# BOARD4.net
KiCad netlist of a schematic drawn in EAGLE
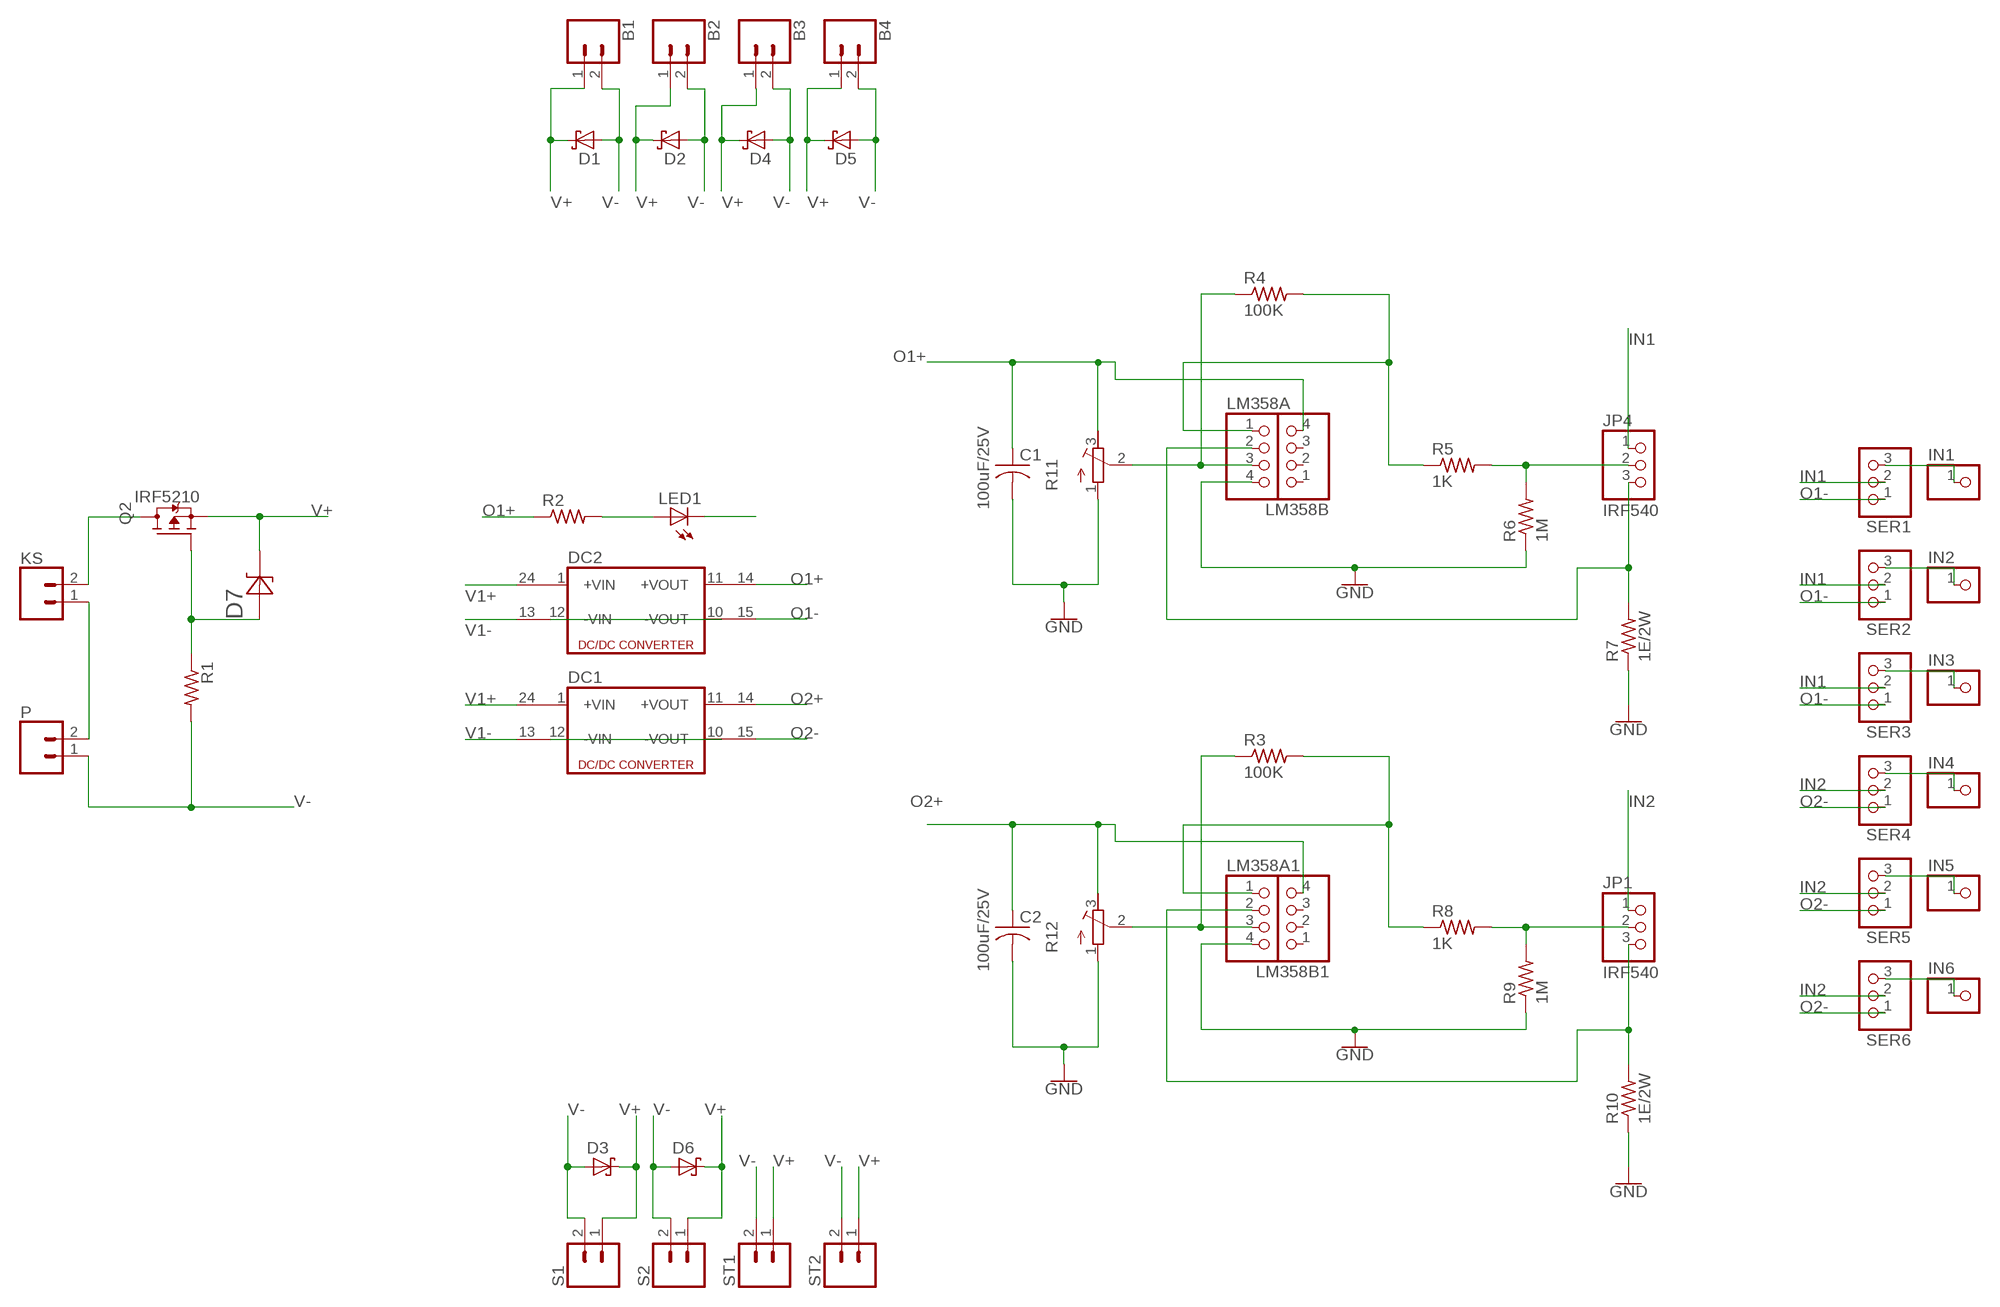
[diagram p0: schematic, sheet 1]

(export (version "E")
  (design (tool "Eeschema 10.0.6"))
  (components
    (comp (ref "B1")
      (value "CONN_02")
      (footprint "eagle-import:1X02")
      (libsource (lib "eagle-import") (part "CONN_02"))
    )
    (comp (ref "B2")
      (value "CONN_02")
      (footprint "eagle-import:1X02")
      (libsource (lib "eagle-import") (part "CONN_02"))
    )
    (comp (ref "B3")
      (value "CONN_02")
      (footprint "eagle-import:1X02")
      (libsource (lib "eagle-import") (part "CONN_02"))
    )
    (comp (ref "B4")
      (value "CONN_02")
      (footprint "eagle-import:1X02")
      (libsource (lib "eagle-import") (part "CONN_02"))
    )
    (comp (ref "C1")
      (value "100uF/25V")
      (footprint "eagle-import:C025-024X044")
      (libsource (lib "eagle-import") (part "C-US025-024X044"))
    )
    (comp (ref "C2")
      (value "100uF/25V")
      (footprint "eagle-import:C025-024X044")
      (libsource (lib "eagle-import") (part "C-US025-024X044"))
    )
    (comp (ref "D1")
      (value "SCHOTTKY-DIODEF126Z12")
      (footprint "eagle-import:F126Z12")
      (libsource (lib "eagle-import") (part "SCHOTTKY-DIODEF126Z12"))
    )
    (comp (ref "D2")
      (value "SCHOTTKY-DIODEF126Z12")
      (footprint "eagle-import:F126Z12")
      (libsource (lib "eagle-import") (part "SCHOTTKY-DIODEF126Z12"))
    )
    (comp (ref "D3")
      (value "SCHOTTKY-DIODEF126Z12")
      (footprint "eagle-import:F126Z12")
      (libsource (lib "eagle-import") (part "SCHOTTKY-DIODEF126Z12"))
    )
    (comp (ref "D4")
      (value "SCHOTTKY-DIODEF126Z12")
      (footprint "eagle-import:F126Z12")
      (libsource (lib "eagle-import") (part "SCHOTTKY-DIODEF126Z12"))
    )
    (comp (ref "D5")
      (value "SCHOTTKY-DIODEF126Z12")
      (footprint "eagle-import:F126Z12")
      (libsource (lib "eagle-import") (part "SCHOTTKY-DIODEF126Z12"))
    )
    (comp (ref "D6")
      (value "SCHOTTKY-DIODEF126Z12")
      (footprint "eagle-import:F126Z12")
      (libsource (lib "eagle-import") (part "SCHOTTKY-DIODEF126Z12"))
    )
    (comp (ref "D7")
      (value "1N4752A-T")
      (footprint "eagle-import:DIOAD1060W80L410D260")
      (fields (field (name "MF") "ON Semiconductor") (field (name "MP") "1N4752A"))
      (libsource (lib "eagle-import") (part "1N4752A-T"))
    )
    (comp (ref "DC1")
      (value "DC213R")
      (footprint "eagle-import:CMK")
      (libsource (lib "eagle-import") (part "DC213R"))
    )
    (comp (ref "DC2")
      (value "DC213R")
      (footprint "eagle-import:CMK")
      (libsource (lib "eagle-import") (part "DC213R"))
    )
    (comp (ref "IN1")
      (value "PINHD-1X1")
      (footprint "eagle-import:1X01")
      (libsource (lib "eagle-import") (part "PINHD-1X1"))
    )
    (comp (ref "IN2")
      (value "PINHD-1X1")
      (footprint "eagle-import:1X01")
      (libsource (lib "eagle-import") (part "PINHD-1X1"))
    )
    (comp (ref "IN3")
      (value "PINHD-1X1")
      (footprint "eagle-import:1X01")
      (libsource (lib "eagle-import") (part "PINHD-1X1"))
    )
    (comp (ref "IN4")
      (value "PINHD-1X1")
      (footprint "eagle-import:1X01")
      (libsource (lib "eagle-import") (part "PINHD-1X1"))
    )
    (comp (ref "IN5")
      (value "PINHD-1X1")
      (footprint "eagle-import:1X01")
      (libsource (lib "eagle-import") (part "PINHD-1X1"))
    )
    (comp (ref "IN6")
      (value "PINHD-1X1")
      (footprint "eagle-import:1X01")
      (libsource (lib "eagle-import") (part "PINHD-1X1"))
    )
    (comp (ref "JP1")
      (value "IRF540")
      (footprint "eagle-import:1X03")
      (libsource (lib "eagle-import") (part "PINHD-1X3"))
    )
    (comp (ref "JP4")
      (value "IRF540")
      (footprint "eagle-import:1X03")
      (libsource (lib "eagle-import") (part "PINHD-1X3"))
    )
    (comp (ref "KS")
      (value "CONN_02")
      (footprint "eagle-import:1X02")
      (libsource (lib "eagle-import") (part "CONN_02"))
    )
    (comp (ref "LED1")
      (value "LED5MM")
      (footprint "eagle-import:LED5MM")
      (libsource (lib "eagle-import") (part "LED5MM"))
    )
    (comp (ref "LM358A")
      (value "PINHD-1X4")
      (footprint "eagle-import:1X04")
      (libsource (lib "eagle-import") (part "PINHD-1X4"))
    )
    (comp (ref "LM358A1")
      (value "PINHD-1X4")
      (footprint "eagle-import:1X04")
      (libsource (lib "eagle-import") (part "PINHD-1X4"))
    )
    (comp (ref "LM358B")
      (value "PINHD-1X4")
      (footprint "eagle-import:1X04")
      (libsource (lib "eagle-import") (part "PINHD-1X4"))
    )
    (comp (ref "LM358B1")
      (value "PINHD-1X4")
      (footprint "eagle-import:1X04")
      (libsource (lib "eagle-import") (part "PINHD-1X4"))
    )
    (comp (ref "P")
      (value "CONN_02")
      (footprint "eagle-import:1X02")
      (libsource (lib "eagle-import") (part "CONN_02"))
    )
    (comp (ref "Q2")
      (value "IRF5210")
      (footprint "eagle-import:TO254P1054X469X2933-3")
      (fields (field (name "MF") "Infineon Technologies"))
      (libsource (lib "eagle-import") (part "IRF5210"))
    )
    (comp (ref "R1")
      (value "R-US_0204/7")
      (footprint "eagle-import:0204_7")
      (libsource (lib "eagle-import") (part "R-US_0204/7"))
    )
    (comp (ref "R2")
      (value "R-US_0204/7")
      (footprint "eagle-import:0204_7")
      (libsource (lib "eagle-import") (part "R-US_0204/7"))
    )
    (comp (ref "R3")
      (value "100K")
      (footprint "eagle-import:0204_5")
      (libsource (lib "eagle-import") (part "R-US_0204/5"))
    )
    (comp (ref "R4")
      (value "100K")
      (footprint "eagle-import:0204_5")
      (libsource (lib "eagle-import") (part "R-US_0204/5"))
    )
    (comp (ref "R5")
      (value "1K")
      (footprint "eagle-import:0204_5")
      (libsource (lib "eagle-import") (part "R-US_0204/5"))
    )
    (comp (ref "R6")
      (value "1M")
      (footprint "eagle-import:0204_5")
      (libsource (lib "eagle-import") (part "R-US_0204/5"))
    )
    (comp (ref "R7")
      (value "1E/2W")
      (footprint "eagle-import:0204_5")
      (libsource (lib "eagle-import") (part "R-US_0204/5"))
    )
    (comp (ref "R8")
      (value "1K")
      (footprint "eagle-import:0204_5")
      (libsource (lib "eagle-import") (part "R-US_0204/5"))
    )
    (comp (ref "R9")
      (value "1M")
      (footprint "eagle-import:0204_5")
      (libsource (lib "eagle-import") (part "R-US_0204/5"))
    )
    (comp (ref "R10")
      (value "1E/2W")
      (footprint "eagle-import:0204_5")
      (libsource (lib "eagle-import") (part "R-US_0204/5"))
    )
    (comp (ref "R11")
      (value "R-TRIMM3339P")
      (footprint "eagle-import:RTRIM3339P")
      (libsource (lib "eagle-import") (part "R-TRIMM3339P"))
    )
    (comp (ref "R12")
      (value "R-TRIMM3339P")
      (footprint "eagle-import:RTRIM3339P")
      (libsource (lib "eagle-import") (part "R-TRIMM3339P"))
    )
    (comp (ref "S1")
      (value "CONN_02")
      (footprint "eagle-import:1X02")
      (libsource (lib "eagle-import") (part "CONN_02"))
    )
    (comp (ref "S2")
      (value "CONN_02")
      (footprint "eagle-import:1X02")
      (libsource (lib "eagle-import") (part "CONN_02"))
    )
    (comp (ref "SER1")
      (value "PINHD-1X3")
      (footprint "eagle-import:1X03")
      (libsource (lib "eagle-import") (part "PINHD-1X3"))
    )
    (comp (ref "SER2")
      (value "PINHD-1X3")
      (footprint "eagle-import:1X03")
      (libsource (lib "eagle-import") (part "PINHD-1X3"))
    )
    (comp (ref "SER3")
      (value "PINHD-1X3")
      (footprint "eagle-import:1X03")
      (libsource (lib "eagle-import") (part "PINHD-1X3"))
    )
    (comp (ref "SER4")
      (value "PINHD-1X3")
      (footprint "eagle-import:1X03")
      (libsource (lib "eagle-import") (part "PINHD-1X3"))
    )
    (comp (ref "SER5")
      (value "PINHD-1X3")
      (footprint "eagle-import:1X03")
      (libsource (lib "eagle-import") (part "PINHD-1X3"))
    )
    (comp (ref "SER6")
      (value "PINHD-1X3")
      (footprint "eagle-import:1X03")
      (libsource (lib "eagle-import") (part "PINHD-1X3"))
    )
    (comp (ref "ST1")
      (value "CONN_02")
      (footprint "eagle-import:1X02")
      (libsource (lib "eagle-import") (part "CONN_02"))
    )
    (comp (ref "ST2")
      (value "CONN_02")
      (footprint "eagle-import:1X02")
      (libsource (lib "eagle-import") (part "CONN_02"))
    )
  )
  (nets
    (net (code "1") (name "/IN1") (class "Default")
      (node (ref "JP4") (pin "1") (pinfunction "1_1") (pintype "passive"))
      (node (ref "SER1") (pin "2") (pinfunction "2_2") (pintype "passive"))
      (node (ref "SER2") (pin "2") (pinfunction "2_2") (pintype "passive"))
      (node (ref "SER3") (pin "2") (pinfunction "2_2") (pintype "passive"))
    )
    (net (code "2") (name "/IN2") (class "Default")
      (node (ref "JP1") (pin "1") (pinfunction "1_1") (pintype "passive"))
      (node (ref "SER4") (pin "2") (pinfunction "2_2") (pintype "passive"))
      (node (ref "SER5") (pin "2") (pinfunction "2_2") (pintype "passive"))
      (node (ref "SER6") (pin "2") (pinfunction "2_2") (pintype "passive"))
    )
    (net (code "3") (name "/O1+") (class "Default")
      (node (ref "C1") (pin "1") (pinfunction "1_1") (pintype "passive"))
      (node (ref "DC2") (pin "14") (pinfunction "+VOUT1_14") (pintype "passive"))
      (node (ref "LM358B") (pin "4") (pinfunction "4_4") (pintype "passive"))
      (node (ref "R11") (pin "3") (pinfunction "E_3") (pintype "passive"))
      (node (ref "R2") (pin "1") (pinfunction "1_1") (pintype "passive"))
    )
    (net (code "4") (name "/O1-") (class "Default")
      (node (ref "DC2") (pin "15") (pinfunction "-VOUT1_15") (pintype "passive"))
      (node (ref "SER1") (pin "1") (pinfunction "1_1") (pintype "passive"))
      (node (ref "SER2") (pin "1") (pinfunction "1_1") (pintype "passive"))
      (node (ref "SER3") (pin "1") (pinfunction "1_1") (pintype "passive"))
    )
    (net (code "5") (name "/O2+") (class "Default")
      (node (ref "C2") (pin "1") (pinfunction "1_1") (pintype "passive"))
      (node (ref "DC1") (pin "14") (pinfunction "+VOUT1_14") (pintype "passive"))
      (node (ref "LM358B1") (pin "4") (pinfunction "4_4") (pintype "passive"))
      (node (ref "R12") (pin "3") (pinfunction "E_3") (pintype "passive"))
    )
    (net (code "6") (name "/O2-") (class "Default")
      (node (ref "DC1") (pin "15") (pinfunction "-VOUT1_15") (pintype "passive"))
      (node (ref "SER4") (pin "1") (pinfunction "1_1") (pintype "passive"))
      (node (ref "SER5") (pin "1") (pinfunction "1_1") (pintype "passive"))
      (node (ref "SER6") (pin "1") (pinfunction "1_1") (pintype "passive"))
    )
    (net (code "7") (name "/V+") (class "Default")
      (node (ref "B1") (pin "1") (pinfunction "1_1") (pintype "passive"))
      (node (ref "B2") (pin "1") (pinfunction "1_1") (pintype "passive"))
      (node (ref "B3") (pin "1") (pinfunction "1_1") (pintype "passive"))
      (node (ref "B4") (pin "1") (pinfunction "1_1") (pintype "passive"))
      (node (ref "D1") (pin "C") (pinfunction "C_C") (pintype "passive"))
      (node (ref "D2") (pin "C") (pinfunction "C_C") (pintype "passive"))
      (node (ref "D3") (pin "C") (pinfunction "C_C") (pintype "passive"))
      (node (ref "D4") (pin "C") (pinfunction "C_C") (pintype "passive"))
      (node (ref "D5") (pin "C") (pinfunction "C_C") (pintype "passive"))
      (node (ref "D6") (pin "C") (pinfunction "C_C") (pintype "passive"))
      (node (ref "D7") (pin "C") (pinfunction "C_C") (pintype "passive"))
      (node (ref "Q2") (pin "3") (pinfunction "S_3") (pintype "passive"))
      (node (ref "S1") (pin "1") (pinfunction "1_1") (pintype "passive"))
      (node (ref "S2") (pin "1") (pinfunction "1_1") (pintype "passive"))
      (node (ref "ST1") (pin "1") (pinfunction "1_1") (pintype "passive"))
      (node (ref "ST2") (pin "1") (pinfunction "1_1") (pintype "passive"))
    )
    (net (code "8") (name "/V-") (class "Default")
      (node (ref "B1") (pin "2") (pinfunction "2_2") (pintype "passive"))
      (node (ref "B2") (pin "2") (pinfunction "2_2") (pintype "passive"))
      (node (ref "B3") (pin "2") (pinfunction "2_2") (pintype "passive"))
      (node (ref "B4") (pin "2") (pinfunction "2_2") (pintype "passive"))
      (node (ref "D1") (pin "A") (pinfunction "A_A") (pintype "passive"))
      (node (ref "D2") (pin "A") (pinfunction "A_A") (pintype "passive"))
      (node (ref "D3") (pin "A") (pinfunction "A_A") (pintype "passive"))
      (node (ref "D4") (pin "A") (pinfunction "A_A") (pintype "passive"))
      (node (ref "D5") (pin "A") (pinfunction "A_A") (pintype "passive"))
      (node (ref "D6") (pin "A") (pinfunction "A_A") (pintype "passive"))
      (node (ref "P") (pin "1") (pinfunction "1_1") (pintype "passive"))
      (node (ref "R1") (pin "2") (pinfunction "2_2") (pintype "passive"))
      (node (ref "S1") (pin "2") (pinfunction "2_2") (pintype "passive"))
      (node (ref "S2") (pin "2") (pinfunction "2_2") (pintype "passive"))
      (node (ref "ST1") (pin "2") (pinfunction "2_2") (pintype "passive"))
      (node (ref "ST2") (pin "2") (pinfunction "2_2") (pintype "passive"))
    )
    (net (code "9") (name "/V1+") (class "Default")
      (node (ref "DC1") (pin "24") (pinfunction "+VIN1_24") (pintype "passive"))
      (node (ref "DC2") (pin "24") (pinfunction "+VIN1_24") (pintype "passive"))
    )
    (net (code "10") (name "/V1-") (class "Default")
      (node (ref "DC1") (pin "13") (pinfunction "-VIN1_13") (pintype "passive"))
      (node (ref "DC2") (pin "13") (pinfunction "-VIN1_13") (pintype "passive"))
    )
    (net (code "11") (name "GND") (class "Default")
      (node (ref "C1") (pin "2") (pinfunction "2_2") (pintype "passive"))
      (node (ref "C2") (pin "2") (pinfunction "2_2") (pintype "passive"))
      (node (ref "LM358A") (pin "4") (pinfunction "4_4") (pintype "passive"))
      (node (ref "LM358A1") (pin "4") (pinfunction "4_4") (pintype "passive"))
      (node (ref "R10") (pin "1") (pinfunction "1_1") (pintype "passive"))
      (node (ref "R11") (pin "1") (pinfunction "A_1") (pintype "passive"))
      (node (ref "R12") (pin "1") (pinfunction "A_1") (pintype "passive"))
      (node (ref "R6") (pin "1") (pinfunction "1_1") (pintype "passive"))
      (node (ref "R7") (pin "1") (pinfunction "1_1") (pintype "passive"))
      (node (ref "R9") (pin "1") (pinfunction "1_1") (pintype "passive"))
    )
    (net (code "12") (name "Net-(DC1--VIN)") (class "Default")
      (node (ref "DC1") (pin "10") (pinfunction "-VOUT_10") (pintype "passive"))
      (node (ref "DC1") (pin "12") (pinfunction "-VIN_12") (pintype "passive"))
    )
    (net (code "13") (name "Net-(DC2--VIN)") (class "Default")
      (node (ref "DC2") (pin "10") (pinfunction "-VOUT_10") (pintype "passive"))
      (node (ref "DC2") (pin "12") (pinfunction "-VIN_12") (pintype "passive"))
    )
    (net (code "14") (name "Net-(IN1-Pad1)") (class "Default")
      (node (ref "IN1") (pin "1") (pinfunction "1_1") (pintype "passive"))
      (node (ref "SER1") (pin "3") (pinfunction "3_3") (pintype "passive"))
    )
    (net (code "15") (name "Net-(IN2-Pad1)") (class "Default")
      (node (ref "IN2") (pin "1") (pinfunction "1_1") (pintype "passive"))
      (node (ref "SER2") (pin "3") (pinfunction "3_3") (pintype "passive"))
    )
    (net (code "16") (name "Net-(IN3-Pad1)") (class "Default")
      (node (ref "IN3") (pin "1") (pinfunction "1_1") (pintype "passive"))
      (node (ref "SER3") (pin "3") (pinfunction "3_3") (pintype "passive"))
    )
    (net (code "17") (name "Net-(IN4-Pad1)") (class "Default")
      (node (ref "IN4") (pin "1") (pinfunction "1_1") (pintype "passive"))
      (node (ref "SER4") (pin "3") (pinfunction "3_3") (pintype "passive"))
    )
    (net (code "18") (name "Net-(IN5-Pad1)") (class "Default")
      (node (ref "IN5") (pin "1") (pinfunction "1_1") (pintype "passive"))
      (node (ref "SER5") (pin "3") (pinfunction "3_3") (pintype "passive"))
    )
    (net (code "19") (name "Net-(IN6-Pad1)") (class "Default")
      (node (ref "IN6") (pin "1") (pinfunction "1_1") (pintype "passive"))
      (node (ref "SER6") (pin "3") (pinfunction "3_3") (pintype "passive"))
    )
    (net (code "20") (name "Net-(JP1-Pad2)") (class "Default")
      (node (ref "JP1") (pin "2") (pinfunction "2_2") (pintype "passive"))
      (node (ref "R8") (pin "2") (pinfunction "2_2") (pintype "passive"))
      (node (ref "R9") (pin "2") (pinfunction "2_2") (pintype "passive"))
    )
    (net (code "21") (name "Net-(JP1-Pad3)") (class "Default")
      (node (ref "JP1") (pin "3") (pinfunction "3_3") (pintype "passive"))
      (node (ref "LM358A1") (pin "2") (pinfunction "2_2") (pintype "passive"))
      (node (ref "R10") (pin "2") (pinfunction "2_2") (pintype "passive"))
    )
    (net (code "22") (name "Net-(JP4-Pad2)") (class "Default")
      (node (ref "JP4") (pin "2") (pinfunction "2_2") (pintype "passive"))
      (node (ref "R5") (pin "2") (pinfunction "2_2") (pintype "passive"))
      (node (ref "R6") (pin "2") (pinfunction "2_2") (pintype "passive"))
    )
    (net (code "23") (name "Net-(JP4-Pad3)") (class "Default")
      (node (ref "JP4") (pin "3") (pinfunction "3_3") (pintype "passive"))
      (node (ref "LM358A") (pin "2") (pinfunction "2_2") (pintype "passive"))
      (node (ref "R7") (pin "2") (pinfunction "2_2") (pintype "passive"))
    )
    (net (code "24") (name "Net-(KS-Pad1)") (class "Default")
      (node (ref "KS") (pin "1") (pinfunction "1_1") (pintype "passive"))
      (node (ref "P") (pin "2") (pinfunction "2_2") (pintype "passive"))
    )
    (net (code "25") (name "Net-(LED1-PadA)") (class "Default")
      (node (ref "LED1") (pin "A") (pinfunction "A_A") (pintype "passive"))
      (node (ref "R2") (pin "2") (pinfunction "2_2") (pintype "passive"))
    )
    (net (code "26") (name "Net-(LM358A-Pad1)") (class "Default")
      (node (ref "LM358A") (pin "1") (pinfunction "1_1") (pintype "passive"))
      (node (ref "R4") (pin "2") (pinfunction "2_2") (pintype "passive"))
      (node (ref "R5") (pin "1") (pinfunction "1_1") (pintype "passive"))
    )
    (net (code "27") (name "Net-(LM358A1-Pad1)") (class "Default")
      (node (ref "LM358A1") (pin "1") (pinfunction "1_1") (pintype "passive"))
      (node (ref "R3") (pin "2") (pinfunction "2_2") (pintype "passive"))
      (node (ref "R8") (pin "1") (pinfunction "1_1") (pintype "passive"))
    )
    (net (code "28") (name "Net-(Q2-D)") (class "Default")
      (node (ref "KS") (pin "2") (pinfunction "2_2") (pintype "passive"))
      (node (ref "Q2") (pin "2") (pinfunction "D_2") (pintype "passive"))
    )
    (net (code "29") (name "Net-(Q2-G)") (class "Default")
      (node (ref "D7") (pin "A") (pinfunction "A_A") (pintype "passive"))
      (node (ref "Q2") (pin "1") (pinfunction "G_1") (pintype "passive"))
      (node (ref "R1") (pin "1") (pinfunction "1_1") (pintype "passive"))
    )
    (net (code "30") (name "Net-(R11-S)") (class "Default")
      (node (ref "LM358A") (pin "3") (pinfunction "3_3") (pintype "passive"))
      (node (ref "R11") (pin "2") (pinfunction "S_2") (pintype "passive"))
      (node (ref "R4") (pin "1") (pinfunction "1_1") (pintype "passive"))
    )
    (net (code "31") (name "Net-(R12-S)") (class "Default")
      (node (ref "LM358A1") (pin "3") (pinfunction "3_3") (pintype "passive"))
      (node (ref "R12") (pin "2") (pinfunction "S_2") (pintype "passive"))
      (node (ref "R3") (pin "1") (pinfunction "1_1") (pintype "passive"))
    )
    (net (code "32") (name "unconnected-(DC1-+VIN-Pad1)") (class "Default")
      (node (ref "DC1") (pin "1") (pinfunction "+VIN_1") (pintype "passive"))
    )
    (net (code "33") (name "unconnected-(DC1-+VOUT-Pad11)") (class "Default")
      (node (ref "DC1") (pin "11") (pinfunction "+VOUT_11") (pintype "passive"))
    )
    (net (code "34") (name "unconnected-(DC2-+VIN-Pad1)") (class "Default")
      (node (ref "DC2") (pin "1") (pinfunction "+VIN_1") (pintype "passive"))
    )
    (net (code "35") (name "unconnected-(DC2-+VOUT-Pad11)") (class "Default")
      (node (ref "DC2") (pin "11") (pinfunction "+VOUT_11") (pintype "passive"))
    )
    (net (code "36") (name "unconnected-(LED1-C-PadK)") (class "Default")
      (node (ref "LED1") (pin "K") (pinfunction "C_K") (pintype "passive"))
    )
    (net (code "37") (name "unconnected-(LM358B-Pad1)") (class "Default")
      (node (ref "LM358B") (pin "1") (pinfunction "1_1") (pintype "passive"))
    )
    (net (code "38") (name "unconnected-(LM358B-Pad2)") (class "Default")
      (node (ref "LM358B") (pin "2") (pinfunction "2_2") (pintype "passive"))
    )
    (net (code "39") (name "unconnected-(LM358B-Pad3)") (class "Default")
      (node (ref "LM358B") (pin "3") (pinfunction "3_3") (pintype "passive"))
    )
    (net (code "40") (name "unconnected-(LM358B1-Pad1)") (class "Default")
      (node (ref "LM358B1") (pin "1") (pinfunction "1_1") (pintype "passive"))
    )
    (net (code "41") (name "unconnected-(LM358B1-Pad2)") (class "Default")
      (node (ref "LM358B1") (pin "2") (pinfunction "2_2") (pintype "passive"))
    )
    (net (code "42") (name "unconnected-(LM358B1-Pad3)") (class "Default")
      (node (ref "LM358B1") (pin "3") (pinfunction "3_3") (pintype "passive"))
    )
  )
)
